# STM32F103C8T6.net
KiCad netlist of a schematic drawn in Altium Designer
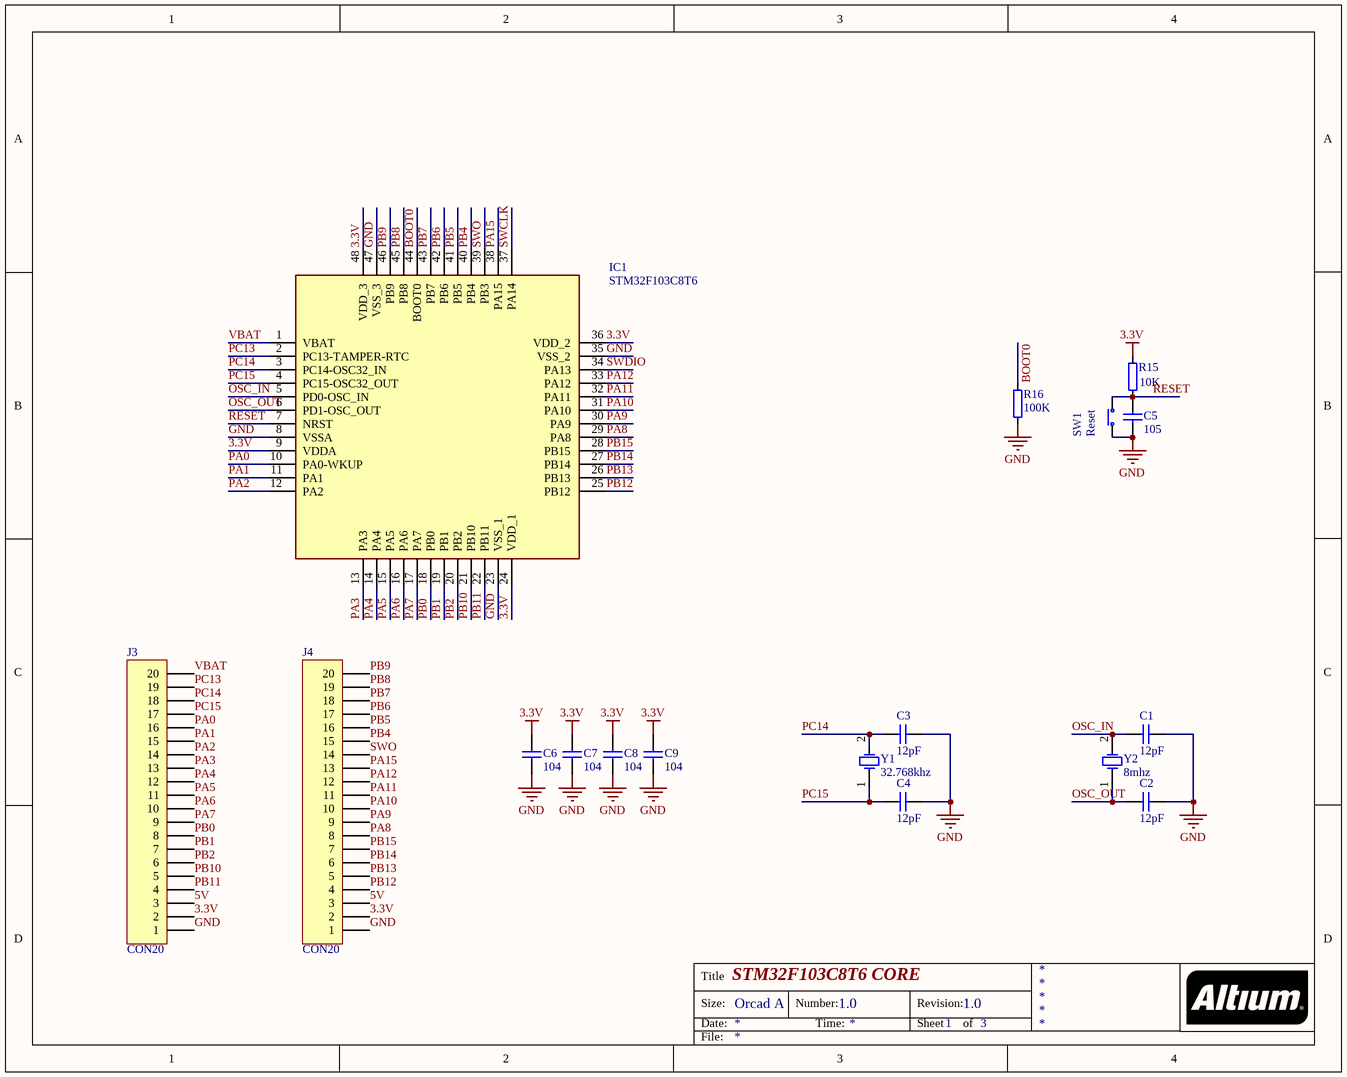
[diagram p0: STM32F103C8T6.SchDoc]

(export (version "E")
  (design (tool "Eeschema 10.0.6"))
  (components
    (comp (ref "C1")
      (value "12pF")
      (footprint "C 0603_L")
      (description "Capacitor, NP0, ?.1pF")
      (fields (field (name "PART NUMBER") "C0402-1.2p") (field (name "PUBLISHER") "Nordic Semiconductor"))
      (libsource (lib "52") (part "CAP"))
    )
    (comp (ref "C2")
      (value "12pF")
      (footprint "C 0603_L")
      (description "Capacitor, NP0, ?.1pF")
      (fields (field (name "PART NUMBER") "C0402-1.2p") (field (name "PUBLISHER") "Nordic Semiconductor"))
      (libsource (lib "52") (part "CAP"))
    )
    (comp (ref "C3")
      (value "12pF")
      (footprint "C 0603_L")
      (description "Capacitor, NP0, ?.1pF")
      (fields (field (name "PART NUMBER") "C0402-1.2p") (field (name "PUBLISHER") "Nordic Semiconductor"))
      (libsource (lib "52") (part "CAP"))
    )
    (comp (ref "C4")
      (value "12pF")
      (footprint "C 0603_L")
      (description "Capacitor, NP0, ?.1pF")
      (fields (field (name "PART NUMBER") "C0402-1.2p") (field (name "PUBLISHER") "Nordic Semiconductor"))
      (libsource (lib "52") (part "CAP"))
    )
    (comp (ref "C5")
      (value "105")
      (footprint "C 0603_L")
      (description "Capacitor, NP0, ?.1pF")
      (fields (field (name "PART NUMBER") "C0402-1.2p") (field (name "PUBLISHER") "Nordic Semiconductor"))
      (libsource (lib "52") (part "CAP"))
    )
    (comp (ref "C6")
      (value "104")
      (footprint "C 0603_L")
      (description "Capacitor, NP0, ?.1pF")
      (fields (field (name "PART NUMBER") "C0402-1.2p") (field (name "PUBLISHER") "Nordic Semiconductor"))
      (libsource (lib "52") (part "CAP"))
    )
    (comp (ref "C7")
      (value "104")
      (footprint "C 0603_L")
      (description "Capacitor, NP0, ?.1pF")
      (fields (field (name "PART NUMBER") "C0402-1.2p") (field (name "PUBLISHER") "Nordic Semiconductor"))
      (libsource (lib "52") (part "CAP"))
    )
    (comp (ref "C8")
      (value "104")
      (footprint "C 0603_L")
      (description "Capacitor, NP0, ?.1pF")
      (fields (field (name "PART NUMBER") "C0402-1.2p") (field (name "PUBLISHER") "Nordic Semiconductor"))
      (libsource (lib "52") (part "CAP"))
    )
    (comp (ref "C9")
      (value "104")
      (footprint "C 0603_L")
      (description "Capacitor, NP0, ?.1pF")
      (fields (field (name "PART NUMBER") "C0402-1.2p") (field (name "PUBLISHER") "Nordic Semiconductor"))
      (libsource (lib "52") (part "CAP"))
    )
    (comp (ref "IC1")
      (value "STM32F103C8T6")
      (footprint "SamacSys:QFP50P900X900X160-48N")
      (description "Integrated Circuit")
      (fields (field (name "MOUSER PART NUMBER") "511-STM32F103C8T6"))
      (libsource (lib "SamacSys") (part "STM32F103C8T6"))
    )
    (comp (ref "J3")
      (value "CON20")
      (footprint "HDR2.54-LI-20P")
      (description "Connector")
      (libsource (lib "插件") (part "CON20"))
    )
    (comp (ref "J4")
      (value "CON20")
      (footprint "HDR2.54-LI-20P")
      (description "Connector")
      (libsource (lib "插件") (part "CON20"))
    )
    (comp (ref "R15") (value "10K") (footprint "R 0603_L") (libsource (lib "电阻") (part "RES")))
    (comp (ref "R16") (value "100K") (footprint "R 0603_L") (libsource (lib "电阻") (part "RES")))
    (comp (ref "SW1")
      (value "Reset")
      (footprint "TSW SMD-6*6*5")
      (description "Tactile Switch, SPNO, SMD, 160gf, 6.2x6.3x2.5mm")
      (fields
        (field (name "PART NUMBER") "Switch-PB-6.2x6.3mm-SMD")
        (field (name "MANUFACTURER") "Dailywell")
        (field (name "PUBLISHER") "Nordic Semiconductor")
      )
      (libsource (lib "52") (part "SW-PB"))
    )
    (comp (ref "Y1") (value "32.768khz") (footprint "OSC 3215-2P") (libsource (lib "我的元件库") (part "XTAL")))
    (comp (ref "Y2") (value "8mhz") (footprint "OSC 5032-2P") (libsource (lib "我的元件库") (part "XTAL")))
  )
  (nets
    (net (code "1") (name "/5V") (class "Default")
      (node (ref "J3") (pin "3") (pinfunction "3_3") (pintype "passive"))
      (node (ref "J4") (pin "3") (pinfunction "3_3") (pintype "passive"))
    )
    (net (code "2") (name "/BOOT0") (class "Default")
      (node (ref "IC1") (pin "44") (pinfunction "BOOT0_44") (pintype "passive"))
      (node (ref "R16") (pin "1") (pinfunction "1_1") (pintype "passive"))
    )
    (net (code "3") (name "/OSC_IN") (class "Default")
      (node (ref "C1") (pin "1") (pinfunction "1_1") (pintype "passive"))
      (node (ref "IC1") (pin "5") (pinfunction "PD0-OSC_IN_5") (pintype "passive"))
      (node (ref "Y2") (pin "2") (pinfunction "2_2") (pintype "passive"))
    )
    (net (code "4") (name "/OSC_OUT") (class "Default")
      (node (ref "C2") (pin "1") (pinfunction "1_1") (pintype "passive"))
      (node (ref "IC1") (pin "6") (pinfunction "PD1-OSC_OUT_6") (pintype "passive"))
      (node (ref "Y2") (pin "1") (pinfunction "1_1") (pintype "passive"))
    )
    (net (code "5") (name "/PA0") (class "Default")
      (node (ref "IC1") (pin "10") (pinfunction "PA0-WKUP_10") (pintype "passive"))
      (node (ref "J3") (pin "16") (pinfunction "16_16") (pintype "passive"))
    )
    (net (code "6") (name "/PA1") (class "Default")
      (node (ref "IC1") (pin "11") (pinfunction "PA1_11") (pintype "passive"))
      (node (ref "J3") (pin "15") (pinfunction "15_15") (pintype "passive"))
    )
    (net (code "7") (name "/PA2") (class "Default")
      (node (ref "IC1") (pin "12") (pinfunction "PA2_12") (pintype "passive"))
      (node (ref "J3") (pin "14") (pinfunction "14_14") (pintype "passive"))
    )
    (net (code "8") (name "/PA3") (class "Default")
      (node (ref "IC1") (pin "13") (pinfunction "PA3_13") (pintype "passive"))
      (node (ref "J3") (pin "13") (pinfunction "13_13") (pintype "passive"))
    )
    (net (code "9") (name "/PA4") (class "Default")
      (node (ref "IC1") (pin "14") (pinfunction "PA4_14") (pintype "passive"))
      (node (ref "J3") (pin "12") (pinfunction "12_12") (pintype "passive"))
    )
    (net (code "10") (name "/PA5") (class "Default")
      (node (ref "IC1") (pin "15") (pinfunction "PA5_15") (pintype "passive"))
      (node (ref "J3") (pin "11") (pinfunction "11_11") (pintype "passive"))
    )
    (net (code "11") (name "/PA6") (class "Default")
      (node (ref "IC1") (pin "16") (pinfunction "PA6_16") (pintype "passive"))
      (node (ref "J3") (pin "10") (pinfunction "10_10") (pintype "passive"))
    )
    (net (code "12") (name "/PA7") (class "Default")
      (node (ref "IC1") (pin "17") (pinfunction "PA7_17") (pintype "passive"))
      (node (ref "J3") (pin "9") (pinfunction "9_9") (pintype "passive"))
    )
    (net (code "13") (name "/PA8") (class "Default")
      (node (ref "IC1") (pin "29") (pinfunction "PA8_29") (pintype "passive"))
      (node (ref "J4") (pin "8") (pinfunction "8_8") (pintype "passive"))
    )
    (net (code "14") (name "/PA9") (class "Default")
      (node (ref "IC1") (pin "30") (pinfunction "PA9_30") (pintype "passive"))
      (node (ref "J4") (pin "9") (pinfunction "9_9") (pintype "passive"))
    )
    (net (code "15") (name "/PA10") (class "Default")
      (node (ref "IC1") (pin "31") (pinfunction "PA10_31") (pintype "passive"))
      (node (ref "J4") (pin "10") (pinfunction "10_10") (pintype "passive"))
    )
    (net (code "16") (name "/PA11") (class "Default")
      (node (ref "IC1") (pin "32") (pinfunction "PA11_32") (pintype "passive"))
      (node (ref "J4") (pin "11") (pinfunction "11_11") (pintype "passive"))
    )
    (net (code "17") (name "/PA12") (class "Default")
      (node (ref "IC1") (pin "33") (pinfunction "PA12_33") (pintype "passive"))
      (node (ref "J4") (pin "12") (pinfunction "12_12") (pintype "passive"))
    )
    (net (code "18") (name "/PA15") (class "Default")
      (node (ref "IC1") (pin "38") (pinfunction "PA15_38") (pintype "passive"))
      (node (ref "J4") (pin "13") (pinfunction "13_13") (pintype "passive"))
    )
    (net (code "19") (name "/PB0") (class "Default")
      (node (ref "IC1") (pin "18") (pinfunction "PB0_18") (pintype "passive"))
      (node (ref "J3") (pin "8") (pinfunction "8_8") (pintype "passive"))
    )
    (net (code "20") (name "/PB1") (class "Default")
      (node (ref "IC1") (pin "19") (pinfunction "PB1_19") (pintype "passive"))
      (node (ref "J3") (pin "7") (pinfunction "7_7") (pintype "passive"))
    )
    (net (code "21") (name "/PB2") (class "Default")
      (node (ref "IC1") (pin "20") (pinfunction "PB2_20") (pintype "passive"))
      (node (ref "J3") (pin "6") (pinfunction "6_6") (pintype "passive"))
    )
    (net (code "22") (name "/PB4") (class "Default")
      (node (ref "IC1") (pin "40") (pinfunction "PB4_40") (pintype "passive"))
      (node (ref "J4") (pin "15") (pinfunction "15_15") (pintype "passive"))
    )
    (net (code "23") (name "/PB5") (class "Default")
      (node (ref "IC1") (pin "41") (pinfunction "PB5_41") (pintype "passive"))
      (node (ref "J4") (pin "16") (pinfunction "16_16") (pintype "passive"))
    )
    (net (code "24") (name "/PB6") (class "Default")
      (node (ref "IC1") (pin "42") (pinfunction "PB6_42") (pintype "passive"))
      (node (ref "J4") (pin "17") (pinfunction "17_17") (pintype "passive"))
    )
    (net (code "25") (name "/PB7") (class "Default")
      (node (ref "IC1") (pin "43") (pinfunction "PB7_43") (pintype "passive"))
      (node (ref "J4") (pin "18") (pinfunction "18_18") (pintype "passive"))
    )
    (net (code "26") (name "/PB8") (class "Default")
      (node (ref "IC1") (pin "45") (pinfunction "PB8_45") (pintype "passive"))
      (node (ref "J4") (pin "19") (pinfunction "19_19") (pintype "passive"))
    )
    (net (code "27") (name "/PB9") (class "Default")
      (node (ref "IC1") (pin "46") (pinfunction "PB9_46") (pintype "passive"))
      (node (ref "J4") (pin "20") (pinfunction "20_20") (pintype "passive"))
    )
    (net (code "28") (name "/PB10") (class "Default")
      (node (ref "IC1") (pin "21") (pinfunction "PB10_21") (pintype "passive"))
      (node (ref "J3") (pin "5") (pinfunction "5_5") (pintype "passive"))
    )
    (net (code "29") (name "/PB11") (class "Default")
      (node (ref "IC1") (pin "22") (pinfunction "PB11_22") (pintype "passive"))
      (node (ref "J3") (pin "4") (pinfunction "4_4") (pintype "passive"))
    )
    (net (code "30") (name "/PB12") (class "Default")
      (node (ref "IC1") (pin "25") (pinfunction "PB12_25") (pintype "passive"))
      (node (ref "J4") (pin "4") (pinfunction "4_4") (pintype "passive"))
    )
    (net (code "31") (name "/PB13") (class "Default")
      (node (ref "IC1") (pin "26") (pinfunction "PB13_26") (pintype "passive"))
      (node (ref "J4") (pin "5") (pinfunction "5_5") (pintype "passive"))
    )
    (net (code "32") (name "/PB14") (class "Default")
      (node (ref "IC1") (pin "27") (pinfunction "PB14_27") (pintype "passive"))
      (node (ref "J4") (pin "6") (pinfunction "6_6") (pintype "passive"))
    )
    (net (code "33") (name "/PB15") (class "Default")
      (node (ref "IC1") (pin "28") (pinfunction "PB15_28") (pintype "passive"))
      (node (ref "J4") (pin "7") (pinfunction "7_7") (pintype "passive"))
    )
    (net (code "34") (name "/PC13") (class "Default")
      (node (ref "IC1") (pin "2") (pinfunction "PC13-TAMPER-RTC_2") (pintype "passive"))
      (node (ref "J3") (pin "19") (pinfunction "19_19") (pintype "passive"))
    )
    (net (code "35") (name "/PC14") (class "Default")
      (node (ref "C3") (pin "1") (pinfunction "1_1") (pintype "passive"))
      (node (ref "IC1") (pin "3") (pinfunction "PC14-OSC32_IN_3") (pintype "passive"))
      (node (ref "J3") (pin "18") (pinfunction "18_18") (pintype "passive"))
      (node (ref "Y1") (pin "2") (pinfunction "2_2") (pintype "passive"))
    )
    (net (code "36") (name "/PC15") (class "Default")
      (node (ref "C4") (pin "1") (pinfunction "1_1") (pintype "passive"))
      (node (ref "IC1") (pin "4") (pinfunction "PC15-OSC32_OUT_4") (pintype "passive"))
      (node (ref "J3") (pin "17") (pinfunction "17_17") (pintype "passive"))
      (node (ref "Y1") (pin "1") (pinfunction "1_1") (pintype "passive"))
    )
    (net (code "37") (name "/RESET") (class "Default")
      (node (ref "C5") (pin "2") (pinfunction "2_2") (pintype "passive"))
      (node (ref "IC1") (pin "7") (pinfunction "NRST_7") (pintype "passive"))
      (node (ref "R15") (pin "1") (pinfunction "1_1") (pintype "passive"))
      (node (ref "SW1") (pin "1") (pinfunction "N.O_1") (pintype "passive"))
    )
    (net (code "38") (name "/SWCLK") (class "Default")
      (node (ref "IC1") (pin "37") (pinfunction "PA14_37") (pintype "passive"))
    )
    (net (code "39") (name "/SWDIO") (class "Default")
      (node (ref "IC1") (pin "34") (pinfunction "PA13_34") (pintype "passive"))
    )
    (net (code "40") (name "/SWO") (class "Default")
      (node (ref "IC1") (pin "39") (pinfunction "PB3_39") (pintype "passive"))
      (node (ref "J4") (pin "14") (pinfunction "14_14") (pintype "passive"))
    )
    (net (code "41") (name "/VBAT") (class "Default")
      (node (ref "IC1") (pin "1") (pinfunction "VBAT_1") (pintype "passive"))
      (node (ref "J3") (pin "20") (pinfunction "20_20") (pintype "passive"))
    )
    (net (code "42") (name "3.3V") (class "Default")
      (node (ref "C6") (pin "2") (pinfunction "2_2") (pintype "passive"))
      (node (ref "C7") (pin "2") (pinfunction "2_2") (pintype "passive"))
      (node (ref "C8") (pin "2") (pinfunction "2_2") (pintype "passive"))
      (node (ref "C9") (pin "2") (pinfunction "2_2") (pintype "passive"))
      (node (ref "IC1") (pin "24") (pinfunction "VDD_1_24") (pintype "passive"))
      (node (ref "IC1") (pin "36") (pinfunction "VDD_2_36") (pintype "passive"))
      (node (ref "IC1") (pin "48") (pinfunction "VDD_3_48") (pintype "passive"))
      (node (ref "IC1") (pin "9") (pinfunction "VDDA_9") (pintype "passive"))
      (node (ref "J3") (pin "2") (pinfunction "2_2") (pintype "passive"))
      (node (ref "J4") (pin "2") (pinfunction "2_2") (pintype "passive"))
      (node (ref "R15") (pin "2") (pinfunction "2_2") (pintype "passive"))
    )
    (net (code "43") (name "GND") (class "Default")
      (node (ref "C1") (pin "2") (pinfunction "2_2") (pintype "passive"))
      (node (ref "C2") (pin "2") (pinfunction "2_2") (pintype "passive"))
      (node (ref "C3") (pin "2") (pinfunction "2_2") (pintype "passive"))
      (node (ref "C4") (pin "2") (pinfunction "2_2") (pintype "passive"))
      (node (ref "C5") (pin "1") (pinfunction "1_1") (pintype "passive"))
      (node (ref "C6") (pin "1") (pinfunction "1_1") (pintype "passive"))
      (node (ref "C7") (pin "1") (pinfunction "1_1") (pintype "passive"))
      (node (ref "C8") (pin "1") (pinfunction "1_1") (pintype "passive"))
      (node (ref "C9") (pin "1") (pinfunction "1_1") (pintype "passive"))
      (node (ref "IC1") (pin "23") (pinfunction "VSS_1_23") (pintype "passive"))
      (node (ref "IC1") (pin "35") (pinfunction "VSS_2_35") (pintype "passive"))
      (node (ref "IC1") (pin "47") (pinfunction "VSS_3_47") (pintype "passive"))
      (node (ref "IC1") (pin "8") (pinfunction "VSSA_8") (pintype "passive"))
      (node (ref "J3") (pin "1") (pinfunction "1_1") (pintype "passive"))
      (node (ref "J4") (pin "1") (pinfunction "1_1") (pintype "passive"))
      (node (ref "R16") (pin "2") (pinfunction "2_2") (pintype "passive"))
      (node (ref "SW1") (pin "2") (pinfunction "COM_2") (pintype "passive"))
    )
  )
)
